# Arduino_Connectors.net
KiCad netlist of a schematic drawn in Altium Designer
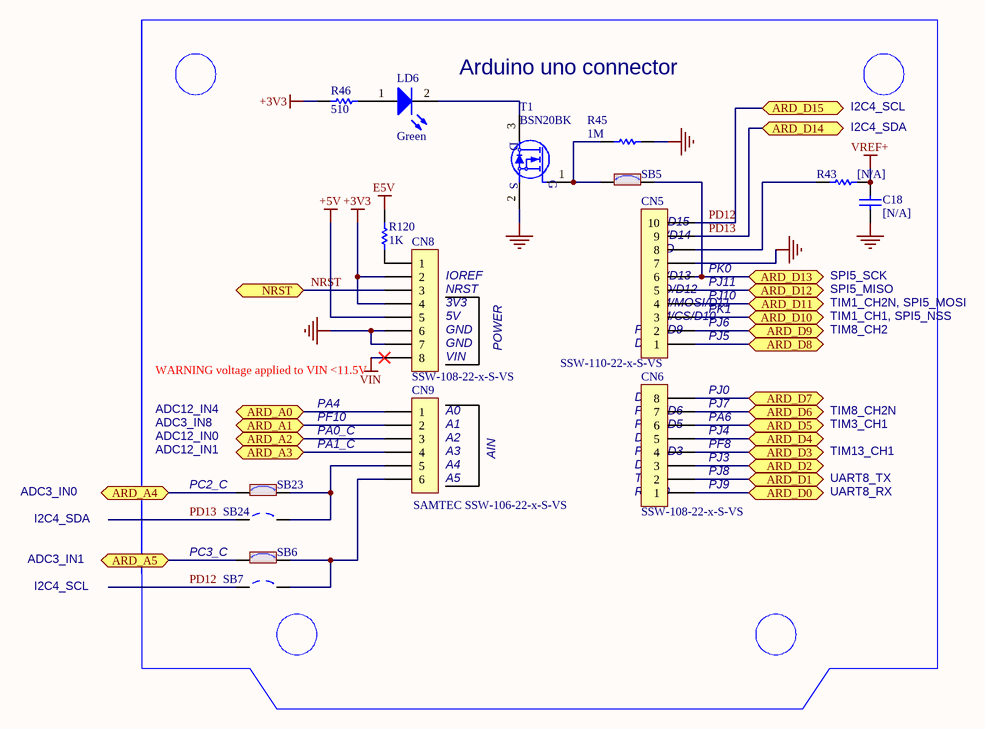
[diagram p0: Arduino_Connectors.SchDoc]

(export (version "E")
  (design (tool "Eeschema 10.0.6"))
  (components
    (comp (ref "C18")
      (value "[N/A]")
      (footprint "0603C")
      (description "Capacitor")
      (fields (field (name "PUBLISHER") "Altium Limited"))
      (libsource (lib "Miscellaneous Devices") (part "Cap"))
    )
    (comp (ref "CN5")
      (value "SSW-110-22-x-S-VS")
      (footprint "SSW-110-22-X-S-VS")
      (description "Header, 10-Pin, Single row,female")
      (fields (field (name "PUBLISHER") "Altium Limited"))
      (libsource (lib "Nucleo_64") (part "Header 10X1_Female"))
    )
    (comp (ref "CN6")
      (value "SSW-108-22-x-S-VS")
      (footprint "SSW-108-22-X-S-VS")
      (description "Header, 8-Pin, Single row,female")
      (fields (field (name "PUBLISHER") "Altium Limited"))
      (libsource (lib "") (part "Header 8X1_Female_1"))
    )
    (comp (ref "CN8")
      (value "SSW-108-22-x-S-VS")
      (footprint "SSW-108-22-X-S-VS")
      (description "Header, 8-Pin, Single row,female")
      (fields (field (name "PUBLISHER") "Altium Limited"))
      (libsource (lib "Nucleo_64") (part "Header 8X1_Female"))
    )
    (comp (ref "CN9")
      (value "SAMTEC SSW-106-22-x-S-VS")
      (footprint "SSW-106-22-X-S-VS")
      (description "Header, 6-Pin, Single row,female SMD")
      (fields (field (name "PUBLISHER") "Altium Limited"))
      (libsource (lib "Nucleo_64") (part "Header 6X1_Female"))
    )
    (comp (ref "LD6")
      (value "Green")
      (footprint "0603D")
      (description "Typical RED, GREEN, YELLOW, AMBER GaAs LED")
      (fields (field (name "PUBLISHER") "Altium Limited"))
      (libsource (lib "Miscellaneous Devices") (part "LED2"))
    )
    (comp (ref "R43")
      (value "[N/A]")
      (footprint "0603R")
      (description "Resistor")
      (fields (field (name "PUBLISHER") "Altium Limited"))
      (libsource (lib "Miscellaneous Devices") (part "res1"))
    )
    (comp (ref "R45")
      (value "1M")
      (footprint "0603R")
      (description "Resistor, 1M , 0603")
      (fields (field (name "PUBLISHER") "Altium Limited"))
      (libsource (lib "Miscellaneous Devices") (part "res1"))
    )
    (comp (ref "R46")
      (value "510")
      (footprint "0603R")
      (description "Resistor")
      (fields (field (name "PUBLISHER") "Altium Limited"))
      (libsource (lib "Miscellaneous Devices") (part "Res1"))
    )
    (comp (ref "R120")
      (value "1K")
      (footprint "0603R")
      (description "Resistor")
      (fields (field (name "PUBLISHER") "Altium Limited"))
      (libsource (lib "Miscellaneous Devices") (part "res1"))
    )
    (comp (ref "SB5")
      (value "Solder Bridge ON")
      (footprint "SB_0603")
      (libsource (lib "MCD_TOOLS") (part "SB_ON"))
    )
    (comp (ref "SB6")
      (value "Solder Bridge ON")
      (footprint "SB_0603")
      (libsource (lib "MCD_TOOLS") (part "SB_ON"))
    )
    (comp (ref "SB7")
      (value "Solder Bridge OFF")
      (footprint "SB_0603")
      (libsource (lib "MCD_TOOLS") (part "SB_OFF"))
    )
    (comp (ref "SB23")
      (value "Solder Bridge ON")
      (footprint "SB_0603")
      (libsource (lib "MCD_TOOLS") (part "SB_ON"))
    )
    (comp (ref "SB24")
      (value "Solder Bridge OFF")
      (footprint "SB_0603")
      (libsource (lib "MCD_TOOLS") (part "SB_OFF"))
    )
    (comp (ref "T1") (value "BSN20BK") (footprint "SOT-23") (libsource (lib "MB525") (part "2N7000")))
  )
  (nets
    (net (code "1") (name "+3V3") (class "Default")
      (node (ref "CN8") (pin "2") (pinfunction "2_2") (pintype "passive"))
      (node (ref "CN8") (pin "4") (pinfunction "4_4") (pintype "passive"))
      (node (ref "R46") (pin "2") (pinfunction "2_2") (pintype "passive"))
    )
    (net (code "2") (name "+5V") (class "Default")
      (node (ref "CN8") (pin "5") (pinfunction "5_5") (pintype "passive"))
    )
    (net (code "3") (name "/ARD_A0") (class "Default")
      (node (ref "CN9") (pin "1") (pinfunction "1_1") (pintype "passive"))
    )
    (net (code "4") (name "/ARD_A1") (class "Default")
      (node (ref "CN9") (pin "2") (pinfunction "2_2") (pintype "passive"))
    )
    (net (code "5") (name "/ARD_A2") (class "Default")
      (node (ref "CN9") (pin "3") (pinfunction "3_3") (pintype "passive"))
    )
    (net (code "6") (name "/ARD_A3") (class "Default")
      (node (ref "CN9") (pin "4") (pinfunction "4_4") (pintype "passive"))
    )
    (net (code "7") (name "/ARD_A4") (class "Default")
      (node (ref "SB23") (pin "1") (pinfunction "1_1") (pintype "passive"))
    )
    (net (code "8") (name "/ARD_A5") (class "Default")
      (node (ref "SB6") (pin "1") (pinfunction "1_1") (pintype "passive"))
    )
    (net (code "9") (name "/ARD_D0") (class "Default")
      (node (ref "CN6") (pin "1") (pinfunction "1_1") (pintype "passive"))
    )
    (net (code "10") (name "/ARD_D1") (class "Default")
      (node (ref "CN6") (pin "2") (pinfunction "2_2") (pintype "passive"))
    )
    (net (code "11") (name "/ARD_D2") (class "Default")
      (node (ref "CN6") (pin "3") (pinfunction "3_3") (pintype "passive"))
    )
    (net (code "12") (name "/ARD_D3") (class "Default")
      (node (ref "CN6") (pin "4") (pinfunction "4_4") (pintype "passive"))
    )
    (net (code "13") (name "/ARD_D4") (class "Default")
      (node (ref "CN6") (pin "5") (pinfunction "5_5") (pintype "passive"))
    )
    (net (code "14") (name "/ARD_D5") (class "Default")
      (node (ref "CN6") (pin "6") (pinfunction "6_6") (pintype "passive"))
    )
    (net (code "15") (name "/ARD_D6") (class "Default")
      (node (ref "CN6") (pin "7") (pinfunction "7_7") (pintype "passive"))
    )
    (net (code "16") (name "/ARD_D7") (class "Default")
      (node (ref "CN6") (pin "8") (pinfunction "8_8") (pintype "passive"))
    )
    (net (code "17") (name "/ARD_D8") (class "Default")
      (node (ref "CN5") (pin "1") (pinfunction "1_1") (pintype "passive"))
    )
    (net (code "18") (name "/ARD_D9") (class "Default")
      (node (ref "CN5") (pin "2") (pinfunction "2_2") (pintype "passive"))
    )
    (net (code "19") (name "/ARD_D10") (class "Default")
      (node (ref "CN5") (pin "3") (pinfunction "3_3") (pintype "passive"))
    )
    (net (code "20") (name "/ARD_D11") (class "Default")
      (node (ref "CN5") (pin "4") (pinfunction "4_4") (pintype "passive"))
    )
    (net (code "21") (name "/ARD_D12") (class "Default")
      (node (ref "CN5") (pin "5") (pinfunction "5_5") (pintype "passive"))
    )
    (net (code "22") (name "/ARD_D13") (class "Default")
      (node (ref "CN5") (pin "6") (pinfunction "6_6") (pintype "passive"))
      (node (ref "SB5") (pin "2") (pinfunction "2_2") (pintype "passive"))
    )
    (net (code "23") (name "/NRST") (class "Default")
      (node (ref "CN8") (pin "3") (pinfunction "3_3") (pintype "passive"))
    )
    (net (code "24") (name "/PD12") (class "Default")
      (node (ref "CN5") (pin "10") (pinfunction "10_10") (pintype "passive"))
      (node (ref "SB7") (pin "1") (pinfunction "1_1") (pintype "passive"))
    )
    (net (code "25") (name "/PD13") (class "Default")
      (node (ref "CN5") (pin "9") (pinfunction "9_9") (pintype "passive"))
      (node (ref "SB24") (pin "1") (pinfunction "1_1") (pintype "passive"))
    )
    (net (code "26") (name "E5V") (class "Default")
      (node (ref "R120") (pin "1") (pinfunction "1_1") (pintype "passive"))
    )
    (net (code "27") (name "GND") (class "Default")
      (node (ref "C18") (pin "1") (pinfunction "1_1") (pintype "passive"))
      (node (ref "CN5") (pin "7") (pinfunction "7_7") (pintype "passive"))
      (node (ref "CN8") (pin "6") (pinfunction "6_6") (pintype "passive"))
      (node (ref "CN8") (pin "7") (pinfunction "7_7") (pintype "passive"))
      (node (ref "R45") (pin "2") (pinfunction "2_2") (pintype "passive"))
      (node (ref "T1") (pin "2") (pinfunction "S_2") (pintype "passive"))
    )
    (net (code "28") (name "Net-(CN5-Pad8)") (class "Default")
      (node (ref "CN5") (pin "8") (pinfunction "8_8") (pintype "passive"))
      (node (ref "R43") (pin "1") (pinfunction "1_1") (pintype "passive"))
    )
    (net (code "29") (name "Net-(CN8-Pad1)") (class "Default")
      (node (ref "CN8") (pin "1") (pinfunction "1_1") (pintype "passive"))
      (node (ref "R120") (pin "2") (pinfunction "2_2") (pintype "passive"))
    )
    (net (code "30") (name "Net-(CN9-Pad5)") (class "Default")
      (node (ref "CN9") (pin "5") (pinfunction "5_5") (pintype "passive"))
      (node (ref "SB23") (pin "2") (pinfunction "2_2") (pintype "passive"))
      (node (ref "SB24") (pin "2") (pinfunction "2_2") (pintype "passive"))
    )
    (net (code "31") (name "Net-(CN9-Pad6)") (class "Default")
      (node (ref "CN9") (pin "6") (pinfunction "6_6") (pintype "passive"))
      (node (ref "SB6") (pin "2") (pinfunction "2_2") (pintype "passive"))
      (node (ref "SB7") (pin "2") (pinfunction "2_2") (pintype "passive"))
    )
    (net (code "32") (name "Net-(LD6-A)") (class "Default")
      (node (ref "LD6") (pin "1") (pinfunction "A_1") (pintype "passive"))
      (node (ref "R46") (pin "1") (pinfunction "1_1") (pintype "passive"))
    )
    (net (code "33") (name "Net-(LD6-K)") (class "Default")
      (node (ref "LD6") (pin "2") (pinfunction "K_2") (pintype "passive"))
      (node (ref "T1") (pin "3") (pinfunction "D_3") (pintype "passive"))
    )
    (net (code "34") (name "Net-(T1-G)") (class "Default")
      (node (ref "R45") (pin "1") (pinfunction "1_1") (pintype "passive"))
      (node (ref "SB5") (pin "1") (pinfunction "1_1") (pintype "passive"))
      (node (ref "T1") (pin "1") (pinfunction "G_1") (pintype "passive"))
    )
    (net (code "35") (name "VIN") (class "Default")
      (node (ref "CN8") (pin "8") (pinfunction "8_8") (pintype "passive"))
    )
    (net (code "36") (name "VREF+") (class "Default")
      (node (ref "C18") (pin "2") (pinfunction "2_2") (pintype "passive"))
      (node (ref "R43") (pin "2") (pinfunction "2_2") (pintype "passive"))
    )
  )
)
